# FLOM_Converter.net
KiCad netlist of a schematic drawn in Altium Designer
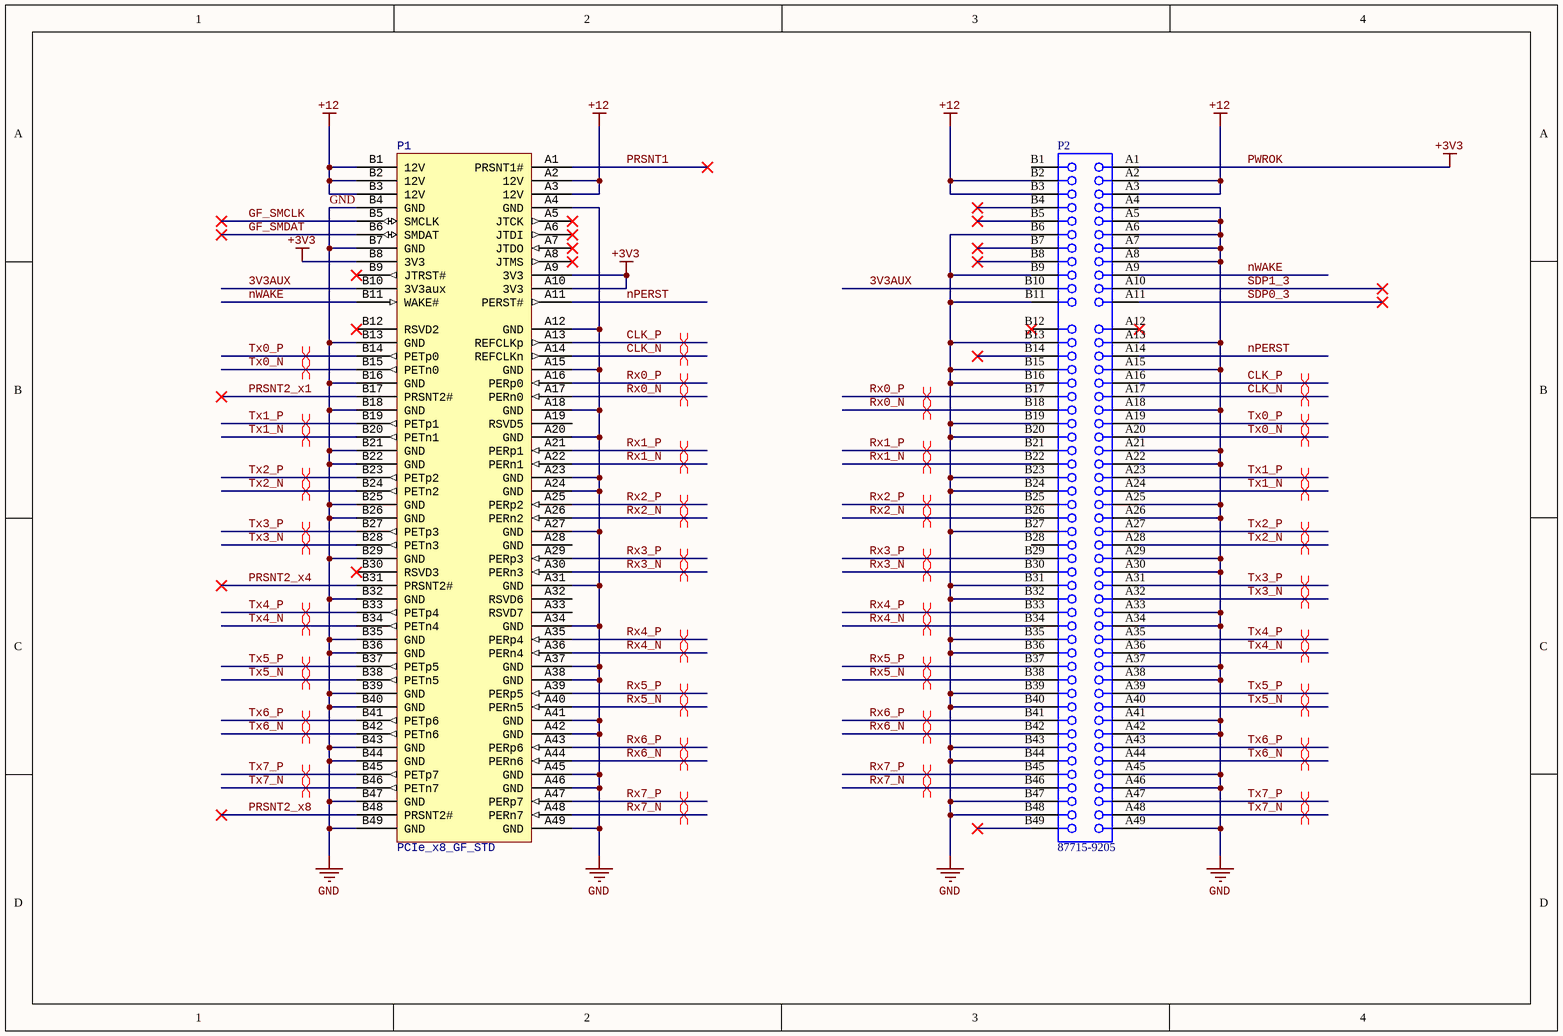
[diagram p0: FLOM_Converter.SchDoc]

(export (version "E")
  (design (tool "Eeschema 10.0.6"))
  (components
    (comp (ref "P1")
      (value "PCIe_x8_GF_STD")
      (footprint "PCIe_x8_GF_STD")
      (libsource (lib "FLOM_Converter") (part "PCIe_x8_GF_STD"))
    )
    (comp (ref "P2")
      (value "87715-9205")
      (footprint "BTB1-00-2V98")
      (description "Board-to-Board Connector, PTH, Vertical, Pitch 1.00mm, 98-Position")
      (fields (field (name "PUBLISHER") "Altium"))
      (libsource (lib "FLOM_Converter") (part "CMP-0001-00128-1"))
    )
  )
  (nets
    (net (code "1") (name "+3V3") (class "Default")
      (node (ref "P1") (pin "A10") (pinfunction "3V3_A10") (pintype "power_in"))
      (node (ref "P1") (pin "A9") (pinfunction "3V3_A9") (pintype "power_in"))
      (node (ref "P1") (pin "B8") (pinfunction "3V3_B8") (pintype "power_in"))
      (node (ref "P2") (pin "A1") (pinfunction "A1_A1") (pintype "passive"))
    )
    (net (code "2") (name "+12") (class "Default")
      (node (ref "P1") (pin "A2") (pinfunction "12V_A2") (pintype "power_in"))
      (node (ref "P1") (pin "A3") (pinfunction "12V_A3") (pintype "power_in"))
      (node (ref "P1") (pin "B1") (pinfunction "12V_B1") (pintype "power_in"))
      (node (ref "P1") (pin "B2") (pinfunction "12V_B2") (pintype "power_in"))
      (node (ref "P1") (pin "B3") (pinfunction "12V_B3") (pintype "power_in"))
      (node (ref "P2") (pin "A2") (pinfunction "A2_A2") (pintype "passive"))
      (node (ref "P2") (pin "A3") (pinfunction "A3_A3") (pintype "passive"))
      (node (ref "P2") (pin "B2") (pinfunction "B2_B2") (pintype "passive"))
      (node (ref "P2") (pin "B3") (pinfunction "B3_B3") (pintype "passive"))
    )
    (net (code "3") (name "/3V3AUX") (class "Default")
      (node (ref "P1") (pin "B10") (pinfunction "3V3aux_B10") (pintype "power_in"))
      (node (ref "P2") (pin "B10") (pinfunction "B10_B10") (pintype "passive"))
    )
    (net (code "5") (name "/CLK_N") (class "Default")
      (node (ref "P1") (pin "A14") (pinfunction "REFCLKn_A14") (pintype "output"))
      (node (ref "P2") (pin "A17") (pinfunction "A17_A17") (pintype "passive"))
    )
    (net (code "6") (name "/CLK_P") (class "Default")
      (node (ref "P1") (pin "A13") (pinfunction "REFCLKp_A13") (pintype "output"))
      (node (ref "P2") (pin "A16") (pinfunction "A16_A16") (pintype "passive"))
    )
    (net (code "7") (name "/GF_SMCLK") (class "Default")
      (node (ref "P1") (pin "B5") (pinfunction "SMCLK_B5") (pintype "bidirectional+no_connect"))
    )
    (net (code "8") (name "/GF_SMDAT") (class "Default")
      (node (ref "P1") (pin "B6") (pinfunction "SMDAT_B6") (pintype "bidirectional+no_connect"))
    )
    (net (code "9") (name "/PRSNT1") (class "Default")
      (node (ref "P1") (pin "A1") (pinfunction "PRSNT1#_A1") (pintype "passive+no_connect"))
    )
    (net (code "10") (name "/PRSNT2_x1") (class "Default")
      (node (ref "P1") (pin "B17") (pinfunction "PRSNT2#_B17") (pintype "passive+no_connect"))
    )
    (net (code "11") (name "/PRSNT2_x4") (class "Default")
      (node (ref "P1") (pin "B31") (pinfunction "PRSNT2#_B31") (pintype "passive+no_connect"))
    )
    (net (code "12") (name "/PRSNT2_x8") (class "Default")
      (node (ref "P1") (pin "B48") (pinfunction "PRSNT2#_B48") (pintype "passive+no_connect"))
    )
    (net (code "13") (name "/Rx0_N") (class "Default")
      (node (ref "P1") (pin "A17") (pinfunction "PERn0_A17") (pintype "input"))
      (node (ref "P2") (pin "B18") (pinfunction "B18_B18") (pintype "passive"))
    )
    (net (code "14") (name "/Rx0_P") (class "Default")
      (node (ref "P1") (pin "A16") (pinfunction "PERp0_A16") (pintype "input"))
      (node (ref "P2") (pin "B17") (pinfunction "B17_B17") (pintype "passive"))
    )
    (net (code "15") (name "/Rx1_N") (class "Default")
      (node (ref "P1") (pin "A22") (pinfunction "PERn1_A22") (pintype "input"))
      (node (ref "P2") (pin "B22") (pinfunction "B22_B22") (pintype "passive"))
    )
    (net (code "16") (name "/Rx1_P") (class "Default")
      (node (ref "P1") (pin "A21") (pinfunction "PERp1_A21") (pintype "input"))
      (node (ref "P2") (pin "B21") (pinfunction "B21_B21") (pintype "passive"))
    )
    (net (code "17") (name "/Rx2_N") (class "Default")
      (node (ref "P1") (pin "A26") (pinfunction "PERn2_A26") (pintype "input"))
      (node (ref "P2") (pin "B26") (pinfunction "B26_B26") (pintype "passive"))
    )
    (net (code "18") (name "/Rx2_P") (class "Default")
      (node (ref "P1") (pin "A25") (pinfunction "PERp2_A25") (pintype "input"))
      (node (ref "P2") (pin "B25") (pinfunction "B25_B25") (pintype "passive"))
    )
    (net (code "19") (name "/Rx3_N") (class "Default")
      (node (ref "P1") (pin "A30") (pinfunction "PERn3_A30") (pintype "input"))
      (node (ref "P2") (pin "B30") (pinfunction "B30_B30") (pintype "passive"))
    )
    (net (code "20") (name "/Rx3_P") (class "Default")
      (node (ref "P1") (pin "A29") (pinfunction "PERp3_A29") (pintype "input"))
      (node (ref "P2") (pin "B29") (pinfunction "B29_B29") (pintype "passive"))
    )
    (net (code "21") (name "/Rx4_N") (class "Default")
      (node (ref "P1") (pin "A36") (pinfunction "PERn4_A36") (pintype "input"))
      (node (ref "P2") (pin "B34") (pinfunction "B34_B34") (pintype "passive"))
    )
    (net (code "22") (name "/Rx4_P") (class "Default")
      (node (ref "P1") (pin "A35") (pinfunction "PERp4_A35") (pintype "input"))
      (node (ref "P2") (pin "B33") (pinfunction "B33_B33") (pintype "passive"))
    )
    (net (code "23") (name "/Rx5_N") (class "Default")
      (node (ref "P1") (pin "A40") (pinfunction "PERn5_A40") (pintype "input"))
      (node (ref "P2") (pin "B38") (pinfunction "B38_B38") (pintype "passive"))
    )
    (net (code "24") (name "/Rx5_P") (class "Default")
      (node (ref "P1") (pin "A39") (pinfunction "PERp5_A39") (pintype "input"))
      (node (ref "P2") (pin "B37") (pinfunction "B37_B37") (pintype "passive"))
    )
    (net (code "25") (name "/Rx6_N") (class "Default")
      (node (ref "P1") (pin "A44") (pinfunction "PERn6_A44") (pintype "input"))
      (node (ref "P2") (pin "B42") (pinfunction "B42_B42") (pintype "passive"))
    )
    (net (code "26") (name "/Rx6_P") (class "Default")
      (node (ref "P1") (pin "A43") (pinfunction "PERp6_A43") (pintype "input"))
      (node (ref "P2") (pin "B41") (pinfunction "B41_B41") (pintype "passive"))
    )
    (net (code "27") (name "/Rx7_N") (class "Default")
      (node (ref "P1") (pin "A48") (pinfunction "PERn7_A48") (pintype "input"))
      (node (ref "P2") (pin "B46") (pinfunction "B46_B46") (pintype "passive"))
    )
    (net (code "28") (name "/Rx7_P") (class "Default")
      (node (ref "P1") (pin "A47") (pinfunction "PERp7_A47") (pintype "input"))
      (node (ref "P2") (pin "B45") (pinfunction "B45_B45") (pintype "passive"))
    )
    (net (code "29") (name "/SDP0_3") (class "Default")
      (node (ref "P2") (pin "A11") (pinfunction "A11_A11") (pintype "passive+no_connect"))
    )
    (net (code "30") (name "/SDP1_3") (class "Default")
      (node (ref "P2") (pin "A10") (pinfunction "A10_A10") (pintype "passive+no_connect"))
    )
    (net (code "31") (name "/Tx0_N") (class "Default")
      (node (ref "P1") (pin "B15") (pinfunction "PETn0_B15") (pintype "output"))
      (node (ref "P2") (pin "A20") (pinfunction "A20_A20") (pintype "passive"))
    )
    (net (code "32") (name "/Tx0_P") (class "Default")
      (node (ref "P1") (pin "B14") (pinfunction "PETp0_B14") (pintype "output"))
      (node (ref "P2") (pin "A19") (pinfunction "A19_A19") (pintype "passive"))
    )
    (net (code "33") (name "/Tx1_N") (class "Default")
      (node (ref "P1") (pin "B20") (pinfunction "PETn1_B20") (pintype "output"))
      (node (ref "P2") (pin "A24") (pinfunction "A24_A24") (pintype "passive"))
    )
    (net (code "34") (name "/Tx1_P") (class "Default")
      (node (ref "P1") (pin "B19") (pinfunction "PETp1_B19") (pintype "output"))
      (node (ref "P2") (pin "A23") (pinfunction "A23_A23") (pintype "passive"))
    )
    (net (code "35") (name "/Tx2_N") (class "Default")
      (node (ref "P1") (pin "B24") (pinfunction "PETn2_B24") (pintype "output"))
      (node (ref "P2") (pin "A28") (pinfunction "A28_A28") (pintype "passive"))
    )
    (net (code "36") (name "/Tx2_P") (class "Default")
      (node (ref "P1") (pin "B23") (pinfunction "PETp2_B23") (pintype "output"))
      (node (ref "P2") (pin "A27") (pinfunction "A27_A27") (pintype "passive"))
    )
    (net (code "37") (name "/Tx3_N") (class "Default")
      (node (ref "P1") (pin "B28") (pinfunction "PETn3_B28") (pintype "output"))
      (node (ref "P2") (pin "A32") (pinfunction "A32_A32") (pintype "passive"))
    )
    (net (code "38") (name "/Tx3_P") (class "Default")
      (node (ref "P1") (pin "B27") (pinfunction "PETp3_B27") (pintype "output"))
      (node (ref "P2") (pin "A31") (pinfunction "A31_A31") (pintype "passive"))
    )
    (net (code "39") (name "/Tx4_N") (class "Default")
      (node (ref "P1") (pin "B34") (pinfunction "PETn4_B34") (pintype "output"))
      (node (ref "P2") (pin "A36") (pinfunction "A36_A36") (pintype "passive"))
    )
    (net (code "40") (name "/Tx4_P") (class "Default")
      (node (ref "P1") (pin "B33") (pinfunction "PETp4_B33") (pintype "output"))
      (node (ref "P2") (pin "A35") (pinfunction "A35_A35") (pintype "passive"))
    )
    (net (code "41") (name "/Tx5_N") (class "Default")
      (node (ref "P1") (pin "B38") (pinfunction "PETn5_B38") (pintype "output"))
      (node (ref "P2") (pin "A40") (pinfunction "A40_A40") (pintype "passive"))
    )
    (net (code "42") (name "/Tx5_P") (class "Default")
      (node (ref "P1") (pin "B37") (pinfunction "PETp5_B37") (pintype "output"))
      (node (ref "P2") (pin "A39") (pinfunction "A39_A39") (pintype "passive"))
    )
    (net (code "43") (name "/Tx6_N") (class "Default")
      (node (ref "P1") (pin "B42") (pinfunction "PETn6_B42") (pintype "output"))
      (node (ref "P2") (pin "A44") (pinfunction "A44_A44") (pintype "passive"))
    )
    (net (code "44") (name "/Tx6_P") (class "Default")
      (node (ref "P1") (pin "B41") (pinfunction "PETp6_B41") (pintype "output"))
      (node (ref "P2") (pin "A43") (pinfunction "A43_A43") (pintype "passive"))
    )
    (net (code "45") (name "/Tx7_N") (class "Default")
      (node (ref "P1") (pin "B46") (pinfunction "PETn7_B46") (pintype "output"))
      (node (ref "P2") (pin "A48") (pinfunction "A48_A48") (pintype "passive"))
    )
    (net (code "46") (name "/Tx7_P") (class "Default")
      (node (ref "P1") (pin "B45") (pinfunction "PETp7_B45") (pintype "output"))
      (node (ref "P2") (pin "A47") (pinfunction "A47_A47") (pintype "passive"))
    )
    (net (code "47") (name "/nPERST") (class "Default")
      (node (ref "P1") (pin "A11") (pinfunction "PERST#_A11") (pintype "output"))
      (node (ref "P2") (pin "A14") (pinfunction "A14_A14") (pintype "passive"))
    )
    (net (code "48") (name "/nWAKE") (class "Default")
      (node (ref "P1") (pin "B11") (pinfunction "WAKE#_B11") (pintype "input"))
      (node (ref "P2") (pin "A9") (pinfunction "A9_A9") (pintype "passive"))
    )
    (net (code "49") (name "GND") (class "Default")
      (node (ref "P1") (pin "A12") (pinfunction "GND_A12") (pintype "power_in"))
      (node (ref "P1") (pin "A15") (pinfunction "GND_A15") (pintype "power_in"))
      (node (ref "P1") (pin "A18") (pinfunction "GND_A18") (pintype "power_in"))
      (node (ref "P1") (pin "A20") (pinfunction "GND_A20") (pintype "power_in"))
      (node (ref "P1") (pin "A23") (pinfunction "GND_A23") (pintype "power_in"))
      (node (ref "P1") (pin "A24") (pinfunction "GND_A24") (pintype "power_in"))
      (node (ref "P1") (pin "A27") (pinfunction "GND_A27") (pintype "power_in"))
      (node (ref "P1") (pin "A31") (pinfunction "GND_A31") (pintype "power_in"))
      (node (ref "P1") (pin "A34") (pinfunction "GND_A34") (pintype "power_in"))
      (node (ref "P1") (pin "A37") (pinfunction "GND_A37") (pintype "power_in"))
      (node (ref "P1") (pin "A38") (pinfunction "GND_A38") (pintype "power_in"))
      (node (ref "P1") (pin "A4") (pinfunction "GND_A4") (pintype "power_in"))
      (node (ref "P1") (pin "A41") (pinfunction "GND_A41") (pintype "power_in"))
      (node (ref "P1") (pin "A42") (pinfunction "GND_A42") (pintype "power_in"))
      (node (ref "P1") (pin "A45") (pinfunction "GND_A45") (pintype "power_in"))
      (node (ref "P1") (pin "A46") (pinfunction "GND_A46") (pintype "power_in"))
      (node (ref "P1") (pin "A49") (pinfunction "GND_A49") (pintype "power_in"))
      (node (ref "P1") (pin "B13") (pinfunction "GND_B13") (pintype "power_in"))
      (node (ref "P1") (pin "B16") (pinfunction "GND_B16") (pintype "power_in"))
      (node (ref "P1") (pin "B18") (pinfunction "GND_B18") (pintype "power_in"))
      (node (ref "P1") (pin "B21") (pinfunction "GND_B21") (pintype "power_in"))
      (node (ref "P1") (pin "B22") (pinfunction "GND_B22") (pintype "power_in"))
      (node (ref "P1") (pin "B25") (pinfunction "GND_B25") (pintype "power_in"))
      (node (ref "P1") (pin "B26") (pinfunction "GND_B26") (pintype "power_in"))
      (node (ref "P1") (pin "B29") (pinfunction "GND_B29") (pintype "power_in"))
      (node (ref "P1") (pin "B32") (pinfunction "GND_B32") (pintype "power_in"))
      (node (ref "P1") (pin "B35") (pinfunction "GND_B35") (pintype "power_in"))
      (node (ref "P1") (pin "B36") (pinfunction "GND_B36") (pintype "power_in"))
      (node (ref "P1") (pin "B39") (pinfunction "GND_B39") (pintype "power_in"))
      (node (ref "P1") (pin "B4") (pinfunction "GND_B4") (pintype "power_in"))
      (node (ref "P1") (pin "B40") (pinfunction "GND_B40") (pintype "power_in"))
      (node (ref "P1") (pin "B43") (pinfunction "GND_B43") (pintype "power_in"))
      (node (ref "P1") (pin "B44") (pinfunction "GND_B44") (pintype "power_in"))
      (node (ref "P1") (pin "B47") (pinfunction "GND_B47") (pintype "power_in"))
      (node (ref "P1") (pin "B49") (pinfunction "GND_B49") (pintype "power_in"))
      (node (ref "P1") (pin "B7") (pinfunction "GND_B7") (pintype "power_in"))
      (node (ref "P2") (pin "A13") (pinfunction "A13_A13") (pintype "passive"))
      (node (ref "P2") (pin "A15") (pinfunction "A15_A15") (pintype "passive"))
      (node (ref "P2") (pin "A18") (pinfunction "A18_A18") (pintype "passive"))
      (node (ref "P2") (pin "A21") (pinfunction "A21_A21") (pintype "passive"))
      (node (ref "P2") (pin "A22") (pinfunction "A22_A22") (pintype "passive"))
      (node (ref "P2") (pin "A25") (pinfunction "A25_A25") (pintype "passive"))
      (node (ref "P2") (pin "A26") (pinfunction "A26_A26") (pintype "passive"))
      (node (ref "P2") (pin "A29") (pinfunction "A29_A29") (pintype "passive"))
      (node (ref "P2") (pin "A30") (pinfunction "A30_A30") (pintype "passive"))
      (node (ref "P2") (pin "A33") (pinfunction "A33_A33") (pintype "passive"))
      (node (ref "P2") (pin "A34") (pinfunction "A34_A34") (pintype "passive"))
      (node (ref "P2") (pin "A37") (pinfunction "A37_A37") (pintype "passive"))
      (node (ref "P2") (pin "A38") (pinfunction "A38_A38") (pintype "passive"))
      (node (ref "P2") (pin "A4") (pinfunction "A4_A4") (pintype "passive"))
      (node (ref "P2") (pin "A41") (pinfunction "A41_A41") (pintype "passive"))
      (node (ref "P2") (pin "A42") (pinfunction "A42_A42") (pintype "passive"))
      (node (ref "P2") (pin "A45") (pinfunction "A45_A45") (pintype "passive"))
      (node (ref "P2") (pin "A46") (pinfunction "A46_A46") (pintype "passive"))
      (node (ref "P2") (pin "A49") (pinfunction "A49_A49") (pintype "passive"))
      (node (ref "P2") (pin "A5") (pinfunction "A5_A5") (pintype "passive"))
      (node (ref "P2") (pin "A6") (pinfunction "A6_A6") (pintype "passive"))
      (node (ref "P2") (pin "A7") (pinfunction "A7_A7") (pintype "passive"))
      (node (ref "P2") (pin "A8") (pinfunction "A8_A8") (pintype "passive"))
      (node (ref "P2") (pin "B11") (pinfunction "B11_B11") (pintype "passive"))
      (node (ref "P2") (pin "B13") (pinfunction "B13_B13") (pintype "passive"))
      (node (ref "P2") (pin "B15") (pinfunction "B15_B15") (pintype "passive"))
      (node (ref "P2") (pin "B16") (pinfunction "B16_B16") (pintype "passive"))
      (node (ref "P2") (pin "B19") (pinfunction "B19_B19") (pintype "passive"))
      (node (ref "P2") (pin "B20") (pinfunction "B20_B20") (pintype "passive"))
      (node (ref "P2") (pin "B23") (pinfunction "B23_B23") (pintype "passive"))
      (node (ref "P2") (pin "B24") (pinfunction "B24_B24") (pintype "passive"))
      (node (ref "P2") (pin "B27") (pinfunction "B27_B27") (pintype "passive"))
      (node (ref "P2") (pin "B31") (pinfunction "B31_B31") (pintype "passive"))
      (node (ref "P2") (pin "B32") (pinfunction "B32_B32") (pintype "passive"))
      (node (ref "P2") (pin "B35") (pinfunction "B35_B35") (pintype "passive"))
      (node (ref "P2") (pin "B36") (pinfunction "B36_B36") (pintype "passive"))
      (node (ref "P2") (pin "B39") (pinfunction "B39_B39") (pintype "passive"))
      (node (ref "P2") (pin "B40") (pinfunction "B40_B40") (pintype "passive"))
      (node (ref "P2") (pin "B43") (pinfunction "B43_B43") (pintype "passive"))
      (node (ref "P2") (pin "B44") (pinfunction "B44_B44") (pintype "passive"))
      (node (ref "P2") (pin "B47") (pinfunction "B47_B47") (pintype "passive"))
      (node (ref "P2") (pin "B48") (pinfunction "B48_B48") (pintype "passive"))
      (node (ref "P2") (pin "B6") (pinfunction "B6_B6") (pintype "passive"))
      (node (ref "P2") (pin "B9") (pinfunction "B9_B9") (pintype "passive"))
    )
    (net (code "50") (name "unconnected-(P1-GND-PadA28)") (class "Default")
      (node (ref "P1") (pin "A28") (pinfunction "GND_A28") (pintype "power_in"))
    )
    (net (code "51") (name "unconnected-(P1-JTCK-PadA5)") (class "Default")
      (node (ref "P1") (pin "A5") (pinfunction "JTCK_A5") (pintype "output+no_connect"))
    )
    (net (code "52") (name "unconnected-(P1-JTDI-PadA6)") (class "Default")
      (node (ref "P1") (pin "A6") (pinfunction "JTDI_A6") (pintype "output+no_connect"))
    )
    (net (code "53") (name "unconnected-(P1-JTDO-PadA7)") (class "Default")
      (node (ref "P1") (pin "A7") (pinfunction "JTDO_A7") (pintype "input+no_connect"))
    )
    (net (code "54") (name "unconnected-(P1-JTMS-PadA8)") (class "Default")
      (node (ref "P1") (pin "A8") (pinfunction "JTMS_A8") (pintype "output+no_connect"))
    )
    (net (code "55") (name "unconnected-(P1-JTRST#-PadB9)") (class "Default")
      (node (ref "P1") (pin "B9") (pinfunction "JTRST#_B9") (pintype "output+no_connect"))
    )
    (net (code "56") (name "unconnected-(P1-RSVD2-PadB12)") (class "Default")
      (node (ref "P1") (pin "B12") (pinfunction "RSVD2_B12") (pintype "passive+no_connect"))
    )
    (net (code "57") (name "unconnected-(P1-RSVD3-PadB30)") (class "Default")
      (node (ref "P1") (pin "B30") (pinfunction "RSVD3_B30") (pintype "passive+no_connect"))
    )
    (net (code "58") (name "unconnected-(P1-RSVD5-PadA19)") (class "Default")
      (node (ref "P1") (pin "A19") (pinfunction "RSVD5_A19") (pintype "passive"))
    )
    (net (code "59") (name "unconnected-(P1-RSVD6-PadA32)") (class "Default")
      (node (ref "P1") (pin "A32") (pinfunction "RSVD6_A32") (pintype "passive"))
    )
    (net (code "60") (name "unconnected-(P1-RSVD7-PadA33)") (class "Default")
      (node (ref "P1") (pin "A33") (pinfunction "RSVD7_A33") (pintype "passive"))
    )
    (net (code "61") (name "unconnected-(P2-PadA12)") (class "Default")
      (node (ref "P2") (pin "A12") (pinfunction "A12_A12") (pintype "passive+no_connect"))
    )
    (net (code "62") (name "unconnected-(P2-PadB1)") (class "Default")
      (node (ref "P2") (pin "B1") (pinfunction "B1_B1") (pintype "passive"))
    )
    (net (code "63") (name "unconnected-(P2-PadB4)") (class "Default")
      (node (ref "P2") (pin "B4") (pinfunction "B4_B4") (pintype "passive+no_connect"))
    )
    (net (code "64") (name "unconnected-(P2-PadB5)") (class "Default")
      (node (ref "P2") (pin "B5") (pinfunction "B5_B5") (pintype "passive+no_connect"))
    )
    (net (code "65") (name "unconnected-(P2-PadB7)") (class "Default")
      (node (ref "P2") (pin "B7") (pinfunction "B7_B7") (pintype "passive+no_connect"))
    )
    (net (code "66") (name "unconnected-(P2-PadB8)") (class "Default")
      (node (ref "P2") (pin "B8") (pinfunction "B8_B8") (pintype "passive+no_connect"))
    )
    (net (code "67") (name "unconnected-(P2-PadB12)") (class "Default")
      (node (ref "P2") (pin "B12") (pinfunction "B12_B12") (pintype "passive+no_connect"))
    )
    (net (code "68") (name "unconnected-(P2-PadB14)") (class "Default")
      (node (ref "P2") (pin "B14") (pinfunction "B14_B14") (pintype "passive+no_connect"))
    )
    (net (code "69") (name "unconnected-(P2-PadB28)") (class "Default")
      (node (ref "P2") (pin "B28") (pinfunction "B28_B28") (pintype "passive"))
    )
    (net (code "70") (name "unconnected-(P2-PadB49)") (class "Default")
      (node (ref "P2") (pin "B49") (pinfunction "B49_B49") (pintype "passive+no_connect"))
    )
  )
)
